# STM32F4xx.net
KiCad netlist of a schematic drawn in Altium Designer
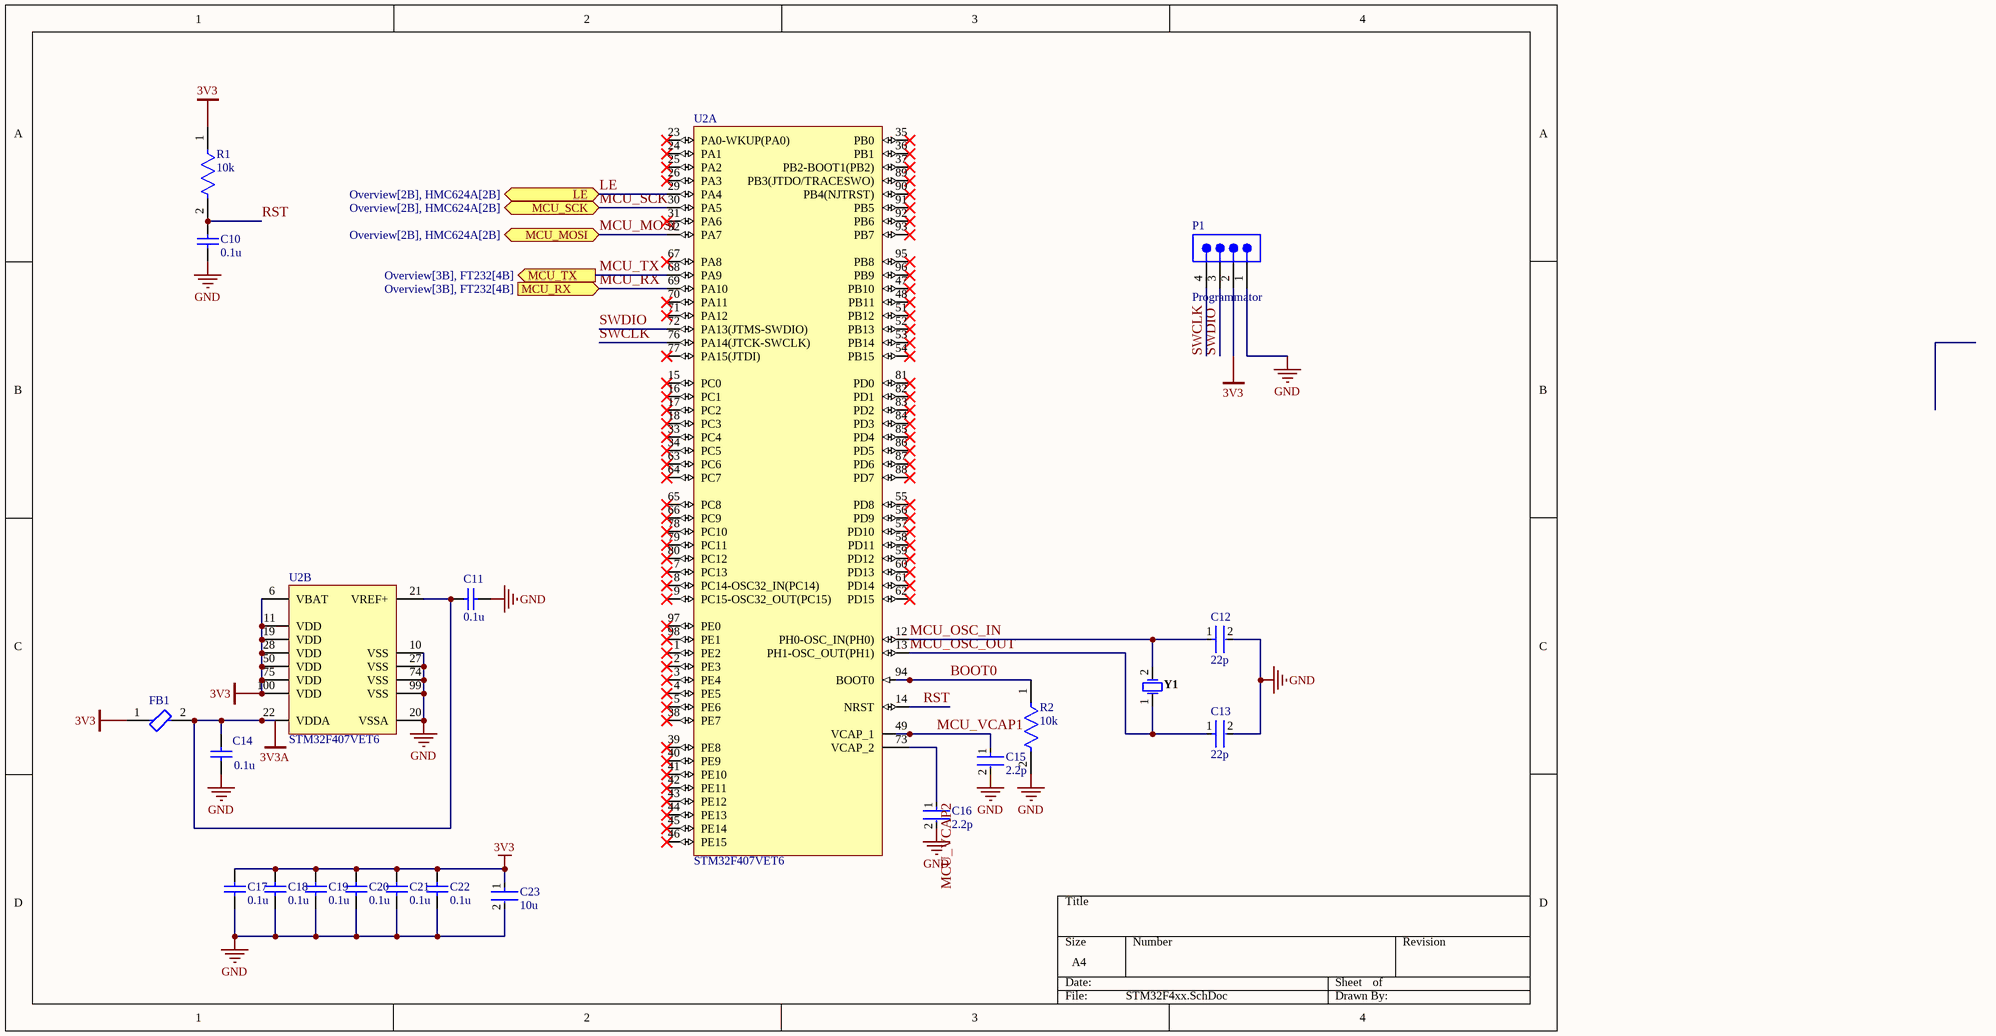
[diagram p0: STM32F4xx.SchDoc]

(export (version "E")
  (design (tool "Eeschema 10.0.6"))
  (components
    (comp (ref "C10")
      (value "0.1u")
      (footprint "CAPC1608X92X38NL15T08")
      (fields (field (name "MANUFACTURER") "Vitramon") (field (name "PART NUMBER") "VJ0603Y104KXXAP"))
      (libsource (lib "Altium Content Vault") (part "CAP"))
    )
    (comp (ref "C11")
      (value "0.1u")
      (footprint "CAPC1608X92X38NL15T08")
      (fields (field (name "MANUFACTURER") "Vitramon") (field (name "PART NUMBER") "VJ0603Y104KXXAP"))
      (libsource (lib "Altium Content Vault") (part "CAP"))
    )
    (comp (ref "C12")
      (value "22p")
      (footprint "FP-C0603C-CF-MFG")
      (description "C0603 22 pF X7R 30ppm/°C 10.00% 100 V")
      (fields
        (field (name "OCTOPART") "https://octopart.com/c0603c220k1racauto-kemet-91893838")
        (field (name "MANUFACTURER PART NUMBER") "C0603C220K1RACAUTO")
      )
      (libsource (lib "Altium Content Vault") (part "b4654b650e69147ec39a6b967a45e02"))
    )
    (comp (ref "C13")
      (value "22p")
      (footprint "FP-C0603C-CF-MFG")
      (description "C0603 22 pF X7R 30ppm/°C 10.00% 100 V")
      (fields
        (field (name "OCTOPART") "https://octopart.com/c0603c220k1racauto-kemet-91893838")
        (field (name "MANUFACTURER PART NUMBER") "C0603C220K1RACAUTO")
      )
      (libsource (lib "Altium Content Vault") (part "b4654b650e69147ec39a6b967a45e02"))
    )
    (comp (ref "C14")
      (value "0.1u")
      (footprint "CAPC1608X92X38NL15T08")
      (fields (field (name "MANUFACTURER") "Vitramon") (field (name "PART NUMBER") "VJ0603Y104KXXAP"))
      (libsource (lib "Altium Content Vault") (part "CAP"))
    )
    (comp (ref "C15")
      (value "2.2p")
      (footprint "FP-CC0603-DA-MFG")
      (description "CC0603 2.2 uF X7R 10.00% 10 V")
      (fields
        (field (name "MANUFACTURER PART NUMBER") "CC0603KPX7R6BB225")
        (field (name "OCTOPART") "https://octopart.com/cc0603kpx7r6bb225-yageo-88116733")
      )
      (libsource (lib "Altium Content Vault") (part "11868f565c42a9108669ba33697ecf6"))
    )
    (comp (ref "C16")
      (value "2.2p")
      (footprint "FP-CC0603-DA-MFG")
      (description "CC0603 2.2 uF X7R 10.00% 10 V")
      (fields
        (field (name "MANUFACTURER PART NUMBER") "CC0603KPX7R6BB225")
        (field (name "OCTOPART") "https://octopart.com/cc0603kpx7r6bb225-yageo-88116733")
      )
      (libsource (lib "Altium Content Vault") (part "11868f565c42a9108669ba33697ecf6"))
    )
    (comp (ref "C17")
      (value "0.1u")
      (footprint "CAPC1608X92X38NL15T08")
      (fields (field (name "MANUFACTURER") "Vitramon") (field (name "PART NUMBER") "VJ0603Y104KXXAP"))
      (libsource (lib "Altium Content Vault") (part "CAP"))
    )
    (comp (ref "C18")
      (value "0.1u")
      (footprint "CAPC1608X92X38NL15T08")
      (fields (field (name "MANUFACTURER") "Vitramon") (field (name "PART NUMBER") "VJ0603Y104KXXAP"))
      (libsource (lib "Altium Content Vault") (part "CAP"))
    )
    (comp (ref "C19")
      (value "0.1u")
      (footprint "CAPC1608X92X38NL15T08")
      (fields (field (name "MANUFACTURER") "Vitramon") (field (name "PART NUMBER") "VJ0603Y104KXXAP"))
      (libsource (lib "Altium Content Vault") (part "CAP"))
    )
    (comp (ref "C20")
      (value "0.1u")
      (footprint "CAPC1608X92X38NL15T08")
      (fields (field (name "MANUFACTURER") "Vitramon") (field (name "PART NUMBER") "VJ0603Y104KXXAP"))
      (libsource (lib "Altium Content Vault") (part "CAP"))
    )
    (comp (ref "C21")
      (value "0.1u")
      (footprint "CAPC1608X92X38NL15T08")
      (fields (field (name "MANUFACTURER") "Vitramon") (field (name "PART NUMBER") "VJ0603Y104KXXAP"))
      (libsource (lib "Altium Content Vault") (part "CAP"))
    )
    (comp (ref "C22")
      (value "0.1u")
      (footprint "CAPC1608X92X38NL15T08")
      (fields (field (name "MANUFACTURER") "Vitramon") (field (name "PART NUMBER") "VJ0603Y104KXXAP"))
      (libsource (lib "Altium Content Vault") (part "CAP"))
    )
    (comp (ref "C23")
      (value "10u")
      (footprint "FP-GRM21B-0_2-e0_2_0_7-MFG")
      (description "Chip Multilayer Ceramic Capacitors for General Purpose, 0805, 10uF, X5R, 15%, 20%, 50V")
      (libsource (lib "Altium Content Vault") (part "b4654b650e69147ec39a6b967a45e02"))
    )
    (comp (ref "FB1")
      (value "BLM21PG600BH1D")
      (footprint "FP-BLM21-0_2-t0_85-e0_5-IPC_C")
      (description "Chip Ferrite Bead, 0805, 60Ω @ 100MHz, 0.02Ω, 25%, 1.9A")
      (libsource (lib "Altium Content Vault") (part "5f30dd21d616792df468990f7003faa"))
    )
    (comp (ref "P1")
      (value "Programmator")
      (footprint "SMTC-TSW-104-08-X-S")
      (description "0.025\" SQ Post Header, Through-hole, Vertical, -55 to 125 degC, 2.54 mm Pitch, 4-Pin, Male, RoHS")
      (fields (field (name "MANUFACTURER") "Samtec") (field (name "PARTNUMBER") "TSW-104-08-G-S"))
      (libsource (lib "Altium Content Vault") (part "SMTC-TSW-104-08-X-S"))
    )
    (comp (ref "R1")
      (value "10k")
      (footprint "FP-AC0603-IPC_A")
      (description "RES 10kΩ 5.00% 0.2W 0603")
      (libsource (lib "Altium Content Vault") (part "1029c3af85768c4190bb7ad29bc67b5"))
    )
    (comp (ref "R2")
      (value "10k")
      (footprint "FP-AC0603-IPC_A")
      (description "RES 10kΩ 5.00% 0.2W 0603")
      (libsource (lib "Altium Content Vault") (part "1029c3af85768c4190bb7ad29bc67b5"))
    )
    (comp (ref "U2")
      (value "STM32F407VET6")
      (footprint "STM-LQFP100_M")
      (fields (field (name "MANUFACTURER") "STMicroelectronics"))
      (libsource (lib "Altium Content Vault") (part "MC-ARM-STM32F40X_41X-SQ100"))
    )
    (comp (ref "Y1")
      (value "NX3225GD-8MHZ-STD-CRA-3")
      (footprint "NDK-NX3225GD-8MHZ-STD-CRA-3_V")
      (description "Crystal Unit, 8 MHz, 8 pF, -40 to 150 degC, 2-Pin SMD, RoHS, Tape and Reel")
      (fields (field (name "MANUFACTURER") "NDK"))
      (libsource (lib "Altium Content Vault") (part "XTAL-1-2-2"))
    )
  )
  (nets
    (net (code "1") (name "/BOOT0") (class "Default")
      (node (ref "R2") (pin "1") (pinfunction "1_1") (pintype "passive"))
      (node (ref "U2") (pin "94") (pinfunction "BOOT0_94") (pintype "input"))
    )
    (net (code "2") (name "/LE") (class "Default")
      (node (ref "U2") (pin "29") (pinfunction "PA4_29") (pintype "bidirectional"))
    )
    (net (code "3") (name "/MCU_MOSI") (class "Default")
      (node (ref "U2") (pin "32") (pinfunction "PA7_32") (pintype "bidirectional"))
    )
    (net (code "4") (name "/MCU_OSC_IN") (class "Default")
      (node (ref "C12") (pin "1") (pinfunction "1_1") (pintype "passive"))
      (node (ref "U2") (pin "12") (pinfunction "PH0-OSC_IN(PH0)_12") (pintype "bidirectional"))
      (node (ref "Y1") (pin "2") (pinfunction "2_2") (pintype "passive"))
    )
    (net (code "5") (name "/MCU_OSC_OUT") (class "Default")
      (node (ref "C13") (pin "1") (pinfunction "1_1") (pintype "passive"))
      (node (ref "U2") (pin "13") (pinfunction "PH1-OSC_OUT(PH1)_13") (pintype "bidirectional"))
      (node (ref "Y1") (pin "1") (pinfunction "1_1") (pintype "passive"))
    )
    (net (code "6") (name "/MCU_RX") (class "Default")
      (node (ref "U2") (pin "69") (pinfunction "PA10_69") (pintype "bidirectional"))
    )
    (net (code "7") (name "/MCU_SCK") (class "Default")
      (node (ref "U2") (pin "30") (pinfunction "PA5_30") (pintype "bidirectional"))
    )
    (net (code "8") (name "/MCU_TX") (class "Default")
      (node (ref "U2") (pin "68") (pinfunction "PA9_68") (pintype "bidirectional"))
    )
    (net (code "9") (name "/MCU_VCAP1") (class "Default")
      (node (ref "C15") (pin "1") (pinfunction "1_1") (pintype "passive"))
      (node (ref "U2") (pin "49") (pinfunction "VCAP_1_49") (pintype "power_in"))
    )
    (net (code "10") (name "/MCU_VCAP2") (class "Default")
      (node (ref "C16") (pin "1") (pinfunction "1_1") (pintype "passive"))
      (node (ref "U2") (pin "73") (pinfunction "VCAP_2_73") (pintype "power_in"))
    )
    (net (code "11") (name "/RST") (class "Default")
      (node (ref "C10") (pin "2") (pinfunction "2_2") (pintype "passive"))
      (node (ref "R1") (pin "2") (pinfunction "2_2") (pintype "passive"))
      (node (ref "U2") (pin "14") (pinfunction "NRST_14") (pintype "bidirectional"))
    )
    (net (code "12") (name "/SWCLK") (class "Default")
      (node (ref "P1") (pin "4") (pinfunction "4_4") (pintype "passive"))
      (node (ref "U2") (pin "76") (pinfunction "PA14(JTCK-SWCLK)_76") (pintype "bidirectional"))
    )
    (net (code "13") (name "/SWDIO") (class "Default")
      (node (ref "P1") (pin "3") (pinfunction "3_3") (pintype "passive"))
      (node (ref "U2") (pin "72") (pinfunction "PA13(JTMS-SWDIO)_72") (pintype "bidirectional"))
    )
    (net (code "14") (name "3V3") (class "Default")
      (node (ref "C17") (pin "2") (pinfunction "2_2") (pintype "passive"))
      (node (ref "C18") (pin "2") (pinfunction "2_2") (pintype "passive"))
      (node (ref "C19") (pin "2") (pinfunction "2_2") (pintype "passive"))
      (node (ref "C20") (pin "2") (pinfunction "2_2") (pintype "passive"))
      (node (ref "C21") (pin "2") (pinfunction "2_2") (pintype "passive"))
      (node (ref "C22") (pin "2") (pinfunction "2_2") (pintype "passive"))
      (node (ref "C23") (pin "1") (pinfunction "1_1") (pintype "passive"))
      (node (ref "FB1") (pin "1") (pinfunction "1_1") (pintype "passive"))
      (node (ref "P1") (pin "2") (pinfunction "2_2") (pintype "passive"))
      (node (ref "R1") (pin "1") (pinfunction "1_1") (pintype "passive"))
      (node (ref "U2") (pin "100") (pinfunction "VDD_100") (pintype "power_in"))
      (node (ref "U2") (pin "11") (pinfunction "VDD_11") (pintype "power_in"))
      (node (ref "U2") (pin "19") (pinfunction "VDD_19") (pintype "power_in"))
      (node (ref "U2") (pin "28") (pinfunction "VDD_28") (pintype "power_in"))
      (node (ref "U2") (pin "50") (pinfunction "VDD_50") (pintype "power_in"))
      (node (ref "U2") (pin "6") (pinfunction "VBAT_6") (pintype "power_in"))
      (node (ref "U2") (pin "75") (pinfunction "VDD_75") (pintype "power_in"))
    )
    (net (code "15") (name "3V3A") (class "Default")
      (node (ref "C11") (pin "2") (pinfunction "2_2") (pintype "passive"))
      (node (ref "C14") (pin "2") (pinfunction "2_2") (pintype "passive"))
      (node (ref "FB1") (pin "2") (pinfunction "2_2") (pintype "passive"))
      (node (ref "U2") (pin "21") (pinfunction "VREF+_21") (pintype "power_in"))
      (node (ref "U2") (pin "22") (pinfunction "VDDA_22") (pintype "power_in"))
    )
    (net (code "16") (name "GND") (class "Default")
      (node (ref "C10") (pin "1") (pinfunction "1_1") (pintype "passive"))
      (node (ref "C11") (pin "1") (pinfunction "1_1") (pintype "passive"))
      (node (ref "C12") (pin "2") (pinfunction "2_2") (pintype "passive"))
      (node (ref "C13") (pin "2") (pinfunction "2_2") (pintype "passive"))
      (node (ref "C14") (pin "1") (pinfunction "1_1") (pintype "passive"))
      (node (ref "C15") (pin "2") (pinfunction "2_2") (pintype "passive"))
      (node (ref "C16") (pin "2") (pinfunction "2_2") (pintype "passive"))
      (node (ref "C17") (pin "1") (pinfunction "1_1") (pintype "passive"))
      (node (ref "C18") (pin "1") (pinfunction "1_1") (pintype "passive"))
      (node (ref "C19") (pin "1") (pinfunction "1_1") (pintype "passive"))
      (node (ref "C20") (pin "1") (pinfunction "1_1") (pintype "passive"))
      (node (ref "C21") (pin "1") (pinfunction "1_1") (pintype "passive"))
      (node (ref "C22") (pin "1") (pinfunction "1_1") (pintype "passive"))
      (node (ref "C23") (pin "2") (pinfunction "2_2") (pintype "passive"))
      (node (ref "P1") (pin "1") (pinfunction "1_1") (pintype "passive"))
      (node (ref "R2") (pin "2") (pinfunction "2_2") (pintype "passive"))
      (node (ref "U2") (pin "10") (pinfunction "VSS_10") (pintype "power_in"))
      (node (ref "U2") (pin "20") (pinfunction "VSSA_20") (pintype "power_in"))
      (node (ref "U2") (pin "27") (pinfunction "VSS_27") (pintype "power_in"))
      (node (ref "U2") (pin "74") (pinfunction "VSS_74") (pintype "power_in"))
      (node (ref "U2") (pin "99") (pinfunction "VSS_99") (pintype "power_in"))
    )
    (net (code "17") (name "unconnected-(U2A-PA0-WKUP(PA0)-Pad23)") (class "Default")
      (node (ref "U2") (pin "23") (pinfunction "PA0-WKUP(PA0)_23") (pintype "bidirectional+no_connect"))
    )
    (net (code "18") (name "unconnected-(U2A-PA1-Pad24)") (class "Default")
      (node (ref "U2") (pin "24") (pinfunction "PA1_24") (pintype "bidirectional+no_connect"))
    )
    (net (code "19") (name "unconnected-(U2A-PA2-Pad25)") (class "Default")
      (node (ref "U2") (pin "25") (pinfunction "PA2_25") (pintype "bidirectional+no_connect"))
    )
    (net (code "20") (name "unconnected-(U2A-PA3-Pad26)") (class "Default")
      (node (ref "U2") (pin "26") (pinfunction "PA3_26") (pintype "bidirectional+no_connect"))
    )
    (net (code "21") (name "unconnected-(U2A-PA6-Pad31)") (class "Default")
      (node (ref "U2") (pin "31") (pinfunction "PA6_31") (pintype "bidirectional+no_connect"))
    )
    (net (code "22") (name "unconnected-(U2A-PA8-Pad67)") (class "Default")
      (node (ref "U2") (pin "67") (pinfunction "PA8_67") (pintype "bidirectional+no_connect"))
    )
    (net (code "23") (name "unconnected-(U2A-PA11-Pad70)") (class "Default")
      (node (ref "U2") (pin "70") (pinfunction "PA11_70") (pintype "bidirectional+no_connect"))
    )
    (net (code "24") (name "unconnected-(U2A-PA12-Pad71)") (class "Default")
      (node (ref "U2") (pin "71") (pinfunction "PA12_71") (pintype "bidirectional+no_connect"))
    )
    (net (code "25") (name "unconnected-(U2A-PA15(JTDI)-Pad77)") (class "Default")
      (node (ref "U2") (pin "77") (pinfunction "PA15(JTDI)_77") (pintype "bidirectional+no_connect"))
    )
    (net (code "26") (name "unconnected-(U2A-PB0-Pad35)") (class "Default")
      (node (ref "U2") (pin "35") (pinfunction "PB0_35") (pintype "bidirectional+no_connect"))
    )
    (net (code "27") (name "unconnected-(U2A-PB1-Pad36)") (class "Default")
      (node (ref "U2") (pin "36") (pinfunction "PB1_36") (pintype "bidirectional+no_connect"))
    )
    (net (code "28") (name "unconnected-(U2A-PB2-BOOT1(PB2)-Pad37)") (class "Default")
      (node (ref "U2") (pin "37") (pinfunction "PB2-BOOT1(PB2)_37") (pintype "bidirectional+no_connect"))
    )
    (net (code "29") (name "unconnected-(U2A-PB3(JTDO{slash}TRACESWO)-Pad89)") (class "Default")
      (node (ref "U2") (pin "89") (pinfunction "PB3(JTDO/TRACESWO)_89") (pintype "bidirectional+no_connect"))
    )
    (net (code "30") (name "unconnected-(U2A-PB4(NJTRST)-Pad90)") (class "Default")
      (node (ref "U2") (pin "90") (pinfunction "PB4(NJTRST)_90") (pintype "bidirectional+no_connect"))
    )
    (net (code "31") (name "unconnected-(U2A-PB5-Pad91)") (class "Default")
      (node (ref "U2") (pin "91") (pinfunction "PB5_91") (pintype "bidirectional+no_connect"))
    )
    (net (code "32") (name "unconnected-(U2A-PB6-Pad92)") (class "Default")
      (node (ref "U2") (pin "92") (pinfunction "PB6_92") (pintype "bidirectional+no_connect"))
    )
    (net (code "33") (name "unconnected-(U2A-PB7-Pad93)") (class "Default")
      (node (ref "U2") (pin "93") (pinfunction "PB7_93") (pintype "bidirectional+no_connect"))
    )
    (net (code "34") (name "unconnected-(U2A-PB8-Pad95)") (class "Default")
      (node (ref "U2") (pin "95") (pinfunction "PB8_95") (pintype "bidirectional+no_connect"))
    )
    (net (code "35") (name "unconnected-(U2A-PB9-Pad96)") (class "Default")
      (node (ref "U2") (pin "96") (pinfunction "PB9_96") (pintype "bidirectional+no_connect"))
    )
    (net (code "36") (name "unconnected-(U2A-PB10-Pad47)") (class "Default")
      (node (ref "U2") (pin "47") (pinfunction "PB10_47") (pintype "bidirectional+no_connect"))
    )
    (net (code "37") (name "unconnected-(U2A-PB11-Pad48)") (class "Default")
      (node (ref "U2") (pin "48") (pinfunction "PB11_48") (pintype "bidirectional+no_connect"))
    )
    (net (code "38") (name "unconnected-(U2A-PB12-Pad51)") (class "Default")
      (node (ref "U2") (pin "51") (pinfunction "PB12_51") (pintype "bidirectional+no_connect"))
    )
    (net (code "39") (name "unconnected-(U2A-PB13-Pad52)") (class "Default")
      (node (ref "U2") (pin "52") (pinfunction "PB13_52") (pintype "bidirectional+no_connect"))
    )
    (net (code "40") (name "unconnected-(U2A-PB14-Pad53)") (class "Default")
      (node (ref "U2") (pin "53") (pinfunction "PB14_53") (pintype "bidirectional+no_connect"))
    )
    (net (code "41") (name "unconnected-(U2A-PB15-Pad54)") (class "Default")
      (node (ref "U2") (pin "54") (pinfunction "PB15_54") (pintype "bidirectional+no_connect"))
    )
    (net (code "42") (name "unconnected-(U2A-PC0-Pad15)") (class "Default")
      (node (ref "U2") (pin "15") (pinfunction "PC0_15") (pintype "bidirectional+no_connect"))
    )
    (net (code "43") (name "unconnected-(U2A-PC1-Pad16)") (class "Default")
      (node (ref "U2") (pin "16") (pinfunction "PC1_16") (pintype "bidirectional+no_connect"))
    )
    (net (code "44") (name "unconnected-(U2A-PC2-Pad17)") (class "Default")
      (node (ref "U2") (pin "17") (pinfunction "PC2_17") (pintype "bidirectional+no_connect"))
    )
    (net (code "45") (name "unconnected-(U2A-PC3-Pad18)") (class "Default")
      (node (ref "U2") (pin "18") (pinfunction "PC3_18") (pintype "bidirectional+no_connect"))
    )
    (net (code "46") (name "unconnected-(U2A-PC4-Pad33)") (class "Default")
      (node (ref "U2") (pin "33") (pinfunction "PC4_33") (pintype "bidirectional+no_connect"))
    )
    (net (code "47") (name "unconnected-(U2A-PC5-Pad34)") (class "Default")
      (node (ref "U2") (pin "34") (pinfunction "PC5_34") (pintype "bidirectional+no_connect"))
    )
    (net (code "48") (name "unconnected-(U2A-PC6-Pad63)") (class "Default")
      (node (ref "U2") (pin "63") (pinfunction "PC6_63") (pintype "bidirectional+no_connect"))
    )
    (net (code "49") (name "unconnected-(U2A-PC7-Pad64)") (class "Default")
      (node (ref "U2") (pin "64") (pinfunction "PC7_64") (pintype "bidirectional+no_connect"))
    )
    (net (code "50") (name "unconnected-(U2A-PC8-Pad65)") (class "Default")
      (node (ref "U2") (pin "65") (pinfunction "PC8_65") (pintype "bidirectional+no_connect"))
    )
    (net (code "51") (name "unconnected-(U2A-PC9-Pad66)") (class "Default")
      (node (ref "U2") (pin "66") (pinfunction "PC9_66") (pintype "bidirectional+no_connect"))
    )
    (net (code "52") (name "unconnected-(U2A-PC10-Pad78)") (class "Default")
      (node (ref "U2") (pin "78") (pinfunction "PC10_78") (pintype "bidirectional+no_connect"))
    )
    (net (code "53") (name "unconnected-(U2A-PC11-Pad79)") (class "Default")
      (node (ref "U2") (pin "79") (pinfunction "PC11_79") (pintype "bidirectional+no_connect"))
    )
    (net (code "54") (name "unconnected-(U2A-PC12-Pad80)") (class "Default")
      (node (ref "U2") (pin "80") (pinfunction "PC12_80") (pintype "bidirectional+no_connect"))
    )
    (net (code "55") (name "unconnected-(U2A-PC13-Pad7)") (class "Default")
      (node (ref "U2") (pin "7") (pinfunction "PC13_7") (pintype "bidirectional+no_connect"))
    )
    (net (code "56") (name "unconnected-(U2A-PC14-OSC32_IN(PC14)-Pad8)") (class "Default")
      (node (ref "U2") (pin "8") (pinfunction "PC14-OSC32_IN(PC14)_8") (pintype "bidirectional+no_connect"))
    )
    (net (code "57") (name "unconnected-(U2A-PC15-OSC32_OUT(PC15)-Pad9)") (class "Default")
      (node (ref "U2") (pin "9") (pinfunction "PC15-OSC32_OUT(PC15)_9") (pintype "bidirectional+no_connect"))
    )
    (net (code "58") (name "unconnected-(U2A-PD0-Pad81)") (class "Default")
      (node (ref "U2") (pin "81") (pinfunction "PD0_81") (pintype "bidirectional+no_connect"))
    )
    (net (code "59") (name "unconnected-(U2A-PD1-Pad82)") (class "Default")
      (node (ref "U2") (pin "82") (pinfunction "PD1_82") (pintype "bidirectional+no_connect"))
    )
    (net (code "60") (name "unconnected-(U2A-PD2-Pad83)") (class "Default")
      (node (ref "U2") (pin "83") (pinfunction "PD2_83") (pintype "bidirectional+no_connect"))
    )
    (net (code "61") (name "unconnected-(U2A-PD3-Pad84)") (class "Default")
      (node (ref "U2") (pin "84") (pinfunction "PD3_84") (pintype "bidirectional+no_connect"))
    )
    (net (code "62") (name "unconnected-(U2A-PD4-Pad85)") (class "Default")
      (node (ref "U2") (pin "85") (pinfunction "PD4_85") (pintype "bidirectional+no_connect"))
    )
    (net (code "63") (name "unconnected-(U2A-PD5-Pad86)") (class "Default")
      (node (ref "U2") (pin "86") (pinfunction "PD5_86") (pintype "bidirectional+no_connect"))
    )
    (net (code "64") (name "unconnected-(U2A-PD6-Pad87)") (class "Default")
      (node (ref "U2") (pin "87") (pinfunction "PD6_87") (pintype "bidirectional+no_connect"))
    )
    (net (code "65") (name "unconnected-(U2A-PD7-Pad88)") (class "Default")
      (node (ref "U2") (pin "88") (pinfunction "PD7_88") (pintype "bidirectional+no_connect"))
    )
    (net (code "66") (name "unconnected-(U2A-PD8-Pad55)") (class "Default")
      (node (ref "U2") (pin "55") (pinfunction "PD8_55") (pintype "bidirectional+no_connect"))
    )
    (net (code "67") (name "unconnected-(U2A-PD9-Pad56)") (class "Default")
      (node (ref "U2") (pin "56") (pinfunction "PD9_56") (pintype "bidirectional+no_connect"))
    )
    (net (code "68") (name "unconnected-(U2A-PD10-Pad57)") (class "Default")
      (node (ref "U2") (pin "57") (pinfunction "PD10_57") (pintype "bidirectional+no_connect"))
    )
    (net (code "69") (name "unconnected-(U2A-PD11-Pad58)") (class "Default")
      (node (ref "U2") (pin "58") (pinfunction "PD11_58") (pintype "bidirectional+no_connect"))
    )
    (net (code "70") (name "unconnected-(U2A-PD12-Pad59)") (class "Default")
      (node (ref "U2") (pin "59") (pinfunction "PD12_59") (pintype "bidirectional+no_connect"))
    )
    (net (code "71") (name "unconnected-(U2A-PD13-Pad60)") (class "Default")
      (node (ref "U2") (pin "60") (pinfunction "PD13_60") (pintype "bidirectional+no_connect"))
    )
    (net (code "72") (name "unconnected-(U2A-PD14-Pad61)") (class "Default")
      (node (ref "U2") (pin "61") (pinfunction "PD14_61") (pintype "bidirectional+no_connect"))
    )
    (net (code "73") (name "unconnected-(U2A-PD15-Pad62)") (class "Default")
      (node (ref "U2") (pin "62") (pinfunction "PD15_62") (pintype "bidirectional+no_connect"))
    )
    (net (code "74") (name "unconnected-(U2A-PE0-Pad97)") (class "Default")
      (node (ref "U2") (pin "97") (pinfunction "PE0_97") (pintype "bidirectional+no_connect"))
    )
    (net (code "75") (name "unconnected-(U2A-PE1-Pad98)") (class "Default")
      (node (ref "U2") (pin "98") (pinfunction "PE1_98") (pintype "bidirectional+no_connect"))
    )
    (net (code "76") (name "unconnected-(U2A-PE2-Pad1)") (class "Default")
      (node (ref "U2") (pin "1") (pinfunction "PE2_1") (pintype "bidirectional+no_connect"))
    )
    (net (code "77") (name "unconnected-(U2A-PE3-Pad2)") (class "Default")
      (node (ref "U2") (pin "2") (pinfunction "PE3_2") (pintype "bidirectional+no_connect"))
    )
    (net (code "78") (name "unconnected-(U2A-PE4-Pad3)") (class "Default")
      (node (ref "U2") (pin "3") (pinfunction "PE4_3") (pintype "bidirectional+no_connect"))
    )
    (net (code "79") (name "unconnected-(U2A-PE5-Pad4)") (class "Default")
      (node (ref "U2") (pin "4") (pinfunction "PE5_4") (pintype "bidirectional+no_connect"))
    )
    (net (code "80") (name "unconnected-(U2A-PE6-Pad5)") (class "Default")
      (node (ref "U2") (pin "5") (pinfunction "PE6_5") (pintype "bidirectional+no_connect"))
    )
    (net (code "81") (name "unconnected-(U2A-PE7-Pad38)") (class "Default")
      (node (ref "U2") (pin "38") (pinfunction "PE7_38") (pintype "bidirectional+no_connect"))
    )
    (net (code "82") (name "unconnected-(U2A-PE8-Pad39)") (class "Default")
      (node (ref "U2") (pin "39") (pinfunction "PE8_39") (pintype "bidirectional+no_connect"))
    )
    (net (code "83") (name "unconnected-(U2A-PE9-Pad40)") (class "Default")
      (node (ref "U2") (pin "40") (pinfunction "PE9_40") (pintype "bidirectional+no_connect"))
    )
    (net (code "84") (name "unconnected-(U2A-PE10-Pad41)") (class "Default")
      (node (ref "U2") (pin "41") (pinfunction "PE10_41") (pintype "bidirectional+no_connect"))
    )
    (net (code "85") (name "unconnected-(U2A-PE11-Pad42)") (class "Default")
      (node (ref "U2") (pin "42") (pinfunction "PE11_42") (pintype "bidirectional+no_connect"))
    )
    (net (code "86") (name "unconnected-(U2A-PE12-Pad43)") (class "Default")
      (node (ref "U2") (pin "43") (pinfunction "PE12_43") (pintype "bidirectional+no_connect"))
    )
    (net (code "87") (name "unconnected-(U2A-PE13-Pad44)") (class "Default")
      (node (ref "U2") (pin "44") (pinfunction "PE13_44") (pintype "bidirectional+no_connect"))
    )
    (net (code "88") (name "unconnected-(U2A-PE14-Pad45)") (class "Default")
      (node (ref "U2") (pin "45") (pinfunction "PE14_45") (pintype "bidirectional+no_connect"))
    )
    (net (code "89") (name "unconnected-(U2A-PE15-Pad46)") (class "Default")
      (node (ref "U2") (pin "46") (pinfunction "PE15_46") (pintype "bidirectional+no_connect"))
    )
  )
)
